# lcd.net
KiCad netlist of a schematic drawn in EAGLE
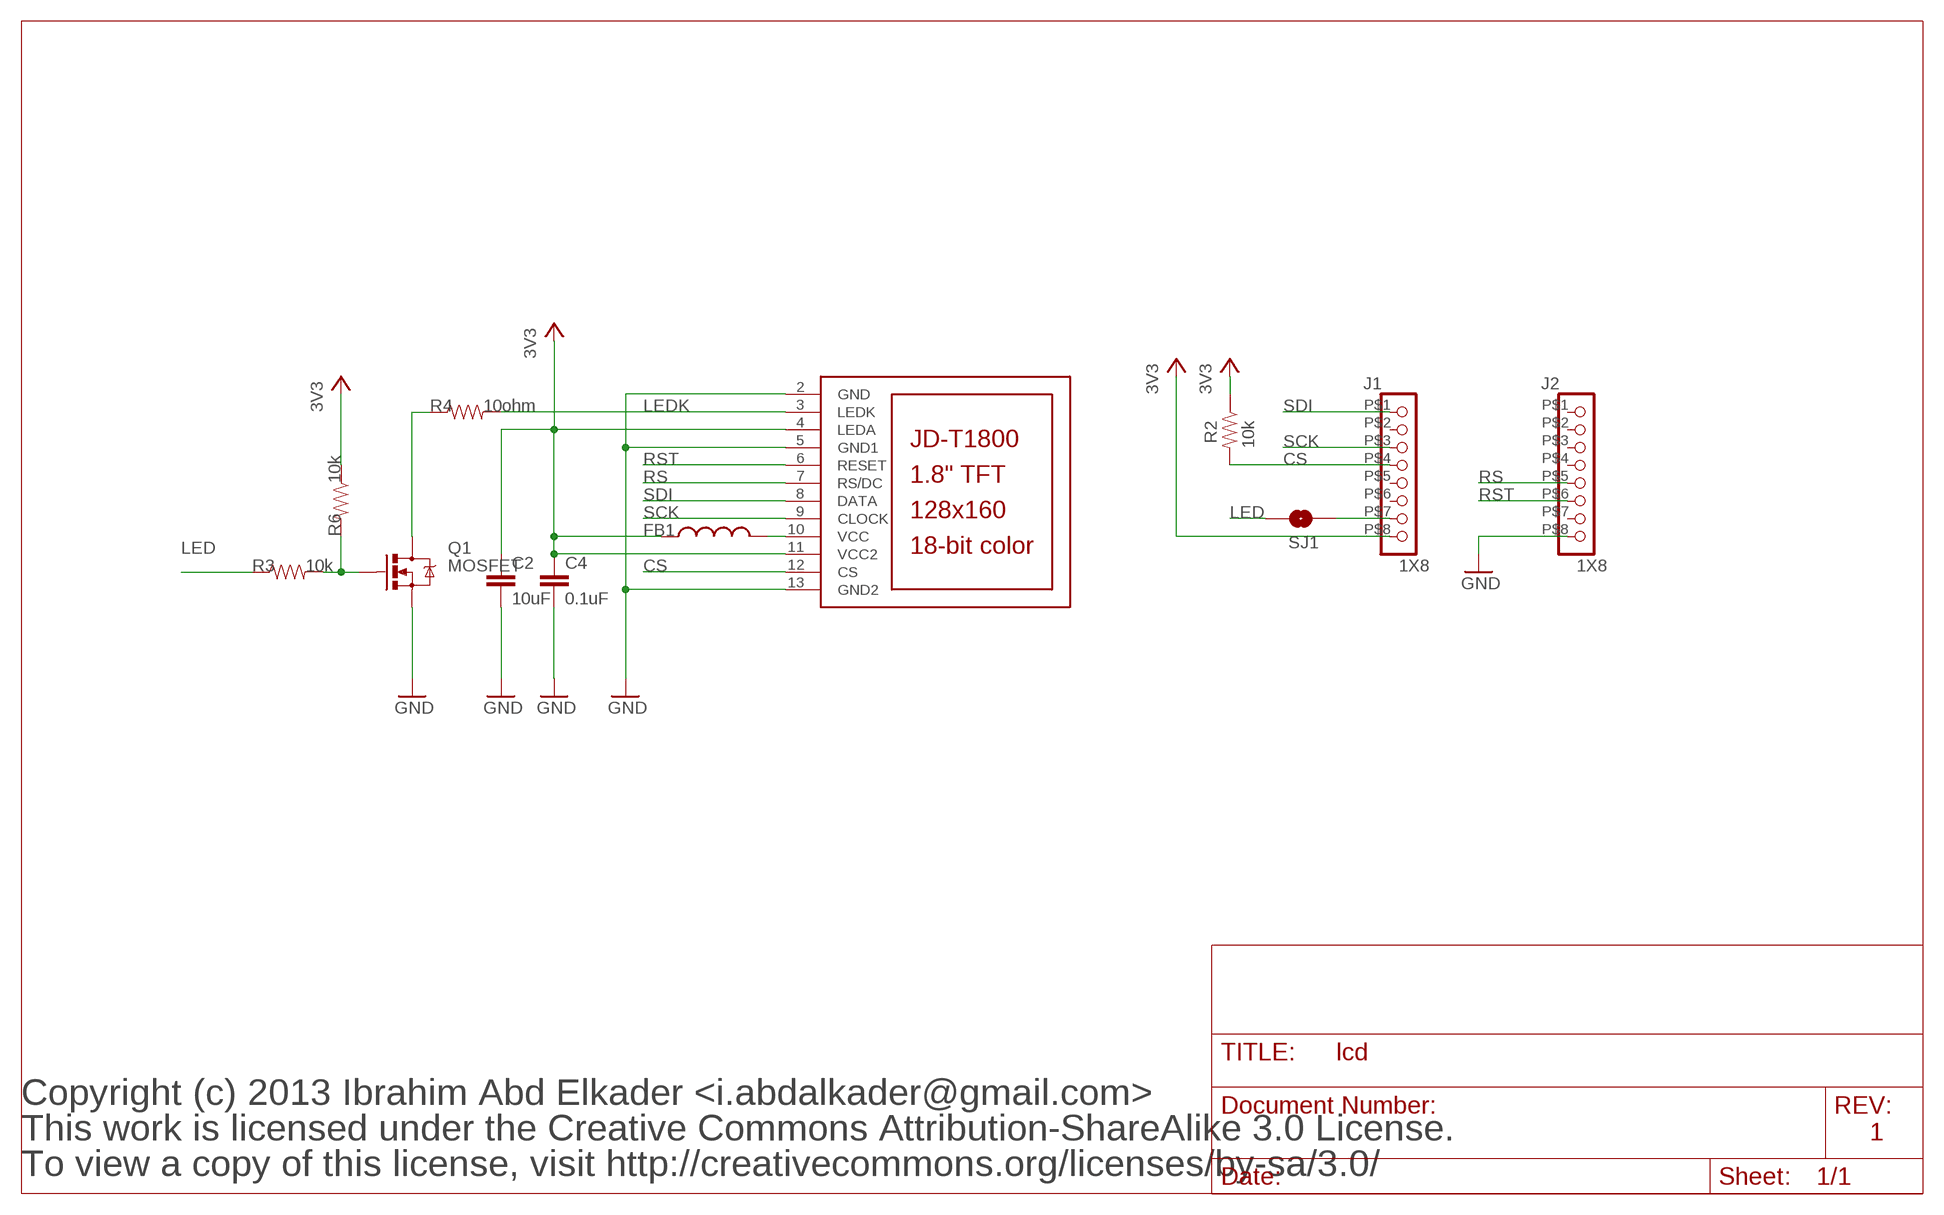
[diagram p0: schematic, sheet 1]

(export (version "E")
  (design (tool "Eeschema 10.0.6"))
  (components
    (comp (ref "C2")
      (value "10uF")
      (footprint "eagle-import:0805")
      (libsource (lib "eagle-import") (part "CAP0805"))
    )
    (comp (ref "C4")
      (value "0.1uF")
      (footprint "eagle-import:0603-CAP")
      (libsource (lib "eagle-import") (part "CAP0603-CAP"))
    )
    (comp (ref "FB1")
      (value "INDUCTOR0603")
      (footprint "eagle-import:0603")
      (libsource (lib "eagle-import") (part "INDUCTOR0603"))
    )
    (comp (ref "J1")
      (value "1X8")
      (footprint "eagle-import:1X8")
      (libsource (lib "eagle-import") (part "1X8"))
    )
    (comp (ref "J2")
      (value "1X8")
      (footprint "eagle-import:1X8")
      (libsource (lib "eagle-import") (part "1X8"))
    )
    (comp (ref "LCD1")
      (value "JD-T1800")
      (footprint "eagle-import:JD-T1800")
      (libsource (lib "eagle-import") (part "JD-T1800"))
    )
    (comp (ref "Q1")
      (value "MOSFET")
      (footprint "eagle-import:SOT23-3")
      (libsource (lib "eagle-import") (part "MOSFET-NCHANNELSMD"))
    )
    (comp (ref "R2")
      (value "10k")
      (footprint "eagle-import:0603-RES")
      (libsource (lib "eagle-import") (part "RESISTOR0603-RES"))
    )
    (comp (ref "R3")
      (value "10k")
      (footprint "eagle-import:0603-RES")
      (libsource (lib "eagle-import") (part "RESISTOR0603-RES"))
    )
    (comp (ref "R4")
      (value "10ohm")
      (footprint "eagle-import:0603-RES")
      (libsource (lib "eagle-import") (part "RESISTOR0603-RES"))
    )
    (comp (ref "R6")
      (value "10k")
      (footprint "eagle-import:0603-RES")
      (libsource (lib "eagle-import") (part "RESISTOR0603-RES"))
    )
    (comp (ref "SJ1")
      (value "SOLDERJUMPERTRACE")
      (footprint "eagle-import:SJ_2S-TRACE")
      (libsource (lib "eagle-import") (part "SOLDERJUMPERTRACE"))
    )
  )
  (nets
    (net (code "1") (name "/CS") (class "Default")
      (node (ref "J1") (pin "P$4") (pinfunction "4_P$4") (pintype "passive"))
      (node (ref "LCD1") (pin "12") (pinfunction "CS_12") (pintype "input"))
      (node (ref "R2") (pin "2") (pinfunction "2_2") (pintype "passive"))
    )
    (net (code "2") (name "/LED") (class "Default")
      (node (ref "R3") (pin "1") (pinfunction "1_1") (pintype "passive"))
      (node (ref "SJ1") (pin "2") (pinfunction "2_2") (pintype "passive"))
    )
    (net (code "3") (name "/LEDK") (class "Default")
      (node (ref "LCD1") (pin "3") (pinfunction "LEDK_3") (pintype "input"))
      (node (ref "R4") (pin "2") (pinfunction "2_2") (pintype "passive"))
    )
    (net (code "4") (name "/RS") (class "Default")
      (node (ref "J2") (pin "P$5") (pinfunction "5_P$5") (pintype "passive"))
      (node (ref "LCD1") (pin "7") (pinfunction "RS/DC_7") (pintype "input"))
    )
    (net (code "5") (name "/RST") (class "Default")
      (node (ref "J2") (pin "P$6") (pinfunction "6_P$6") (pintype "passive"))
      (node (ref "LCD1") (pin "6") (pinfunction "RESET_6") (pintype "input"))
    )
    (net (code "6") (name "/SCK") (class "Default")
      (node (ref "J1") (pin "P$3") (pinfunction "3_P$3") (pintype "passive"))
      (node (ref "LCD1") (pin "9") (pinfunction "CLOCK_9") (pintype "input"))
    )
    (net (code "7") (name "/SDI") (class "Default")
      (node (ref "J1") (pin "P$1") (pinfunction "1_P$1") (pintype "passive"))
      (node (ref "LCD1") (pin "8") (pinfunction "DATA_8") (pintype "bidirectional"))
    )
    (net (code "8") (name "3V3") (class "Default")
      (node (ref "C2") (pin "1") (pinfunction "1_1") (pintype "passive"))
      (node (ref "C4") (pin "1") (pinfunction "1_1") (pintype "passive"))
      (node (ref "FB1") (pin "1") (pinfunction "1_1") (pintype "passive"))
      (node (ref "J1") (pin "P$8") (pinfunction "8_P$8") (pintype "passive"))
      (node (ref "LCD1") (pin "11") (pinfunction "VCC2_11") (pintype "power_in"))
      (node (ref "LCD1") (pin "4") (pinfunction "LEDA_4") (pintype "input"))
      (node (ref "R2") (pin "1") (pinfunction "1_1") (pintype "passive"))
      (node (ref "R6") (pin "1") (pinfunction "1_1") (pintype "passive"))
    )
    (net (code "9") (name "GND") (class "Default")
      (node (ref "C2") (pin "2") (pinfunction "2_2") (pintype "passive"))
      (node (ref "C4") (pin "2") (pinfunction "2_2") (pintype "passive"))
      (node (ref "J2") (pin "P$8") (pinfunction "8_P$8") (pintype "passive"))
      (node (ref "LCD1") (pin "13") (pinfunction "GND2_13") (pintype "power_in"))
      (node (ref "LCD1") (pin "2") (pinfunction "GND_2") (pintype "power_in"))
      (node (ref "LCD1") (pin "5") (pinfunction "GND1_5") (pintype "power_in"))
      (node (ref "Q1") (pin "2") (pinfunction "S_2") (pintype "passive"))
    )
    (net (code "10") (name "Net-(J1-7)") (class "Default")
      (node (ref "J1") (pin "P$7") (pinfunction "7_P$7") (pintype "passive"))
      (node (ref "SJ1") (pin "1") (pinfunction "1_1") (pintype "passive"))
    )
    (net (code "11") (name "Net-(LCD1-VCC)") (class "Default")
      (node (ref "FB1") (pin "2") (pinfunction "2_2") (pintype "passive"))
      (node (ref "LCD1") (pin "10") (pinfunction "VCC_10") (pintype "power_in"))
    )
    (net (code "12") (name "Net-(Q1-D)") (class "Default")
      (node (ref "Q1") (pin "3") (pinfunction "D_3") (pintype "passive"))
      (node (ref "R4") (pin "1") (pinfunction "1_1") (pintype "passive"))
    )
    (net (code "13") (name "Net-(Q1-G)") (class "Default")
      (node (ref "Q1") (pin "1") (pinfunction "G_1") (pintype "passive"))
      (node (ref "R3") (pin "2") (pinfunction "2_2") (pintype "passive"))
      (node (ref "R6") (pin "2") (pinfunction "2_2") (pintype "passive"))
    )
    (net (code "14") (name "unconnected-(J1-2-PadP$2)") (class "Default")
      (node (ref "J1") (pin "P$2") (pinfunction "2_P$2") (pintype "passive"))
    )
    (net (code "15") (name "unconnected-(J1-5-PadP$5)") (class "Default")
      (node (ref "J1") (pin "P$5") (pinfunction "5_P$5") (pintype "passive"))
    )
    (net (code "16") (name "unconnected-(J1-6-PadP$6)") (class "Default")
      (node (ref "J1") (pin "P$6") (pinfunction "6_P$6") (pintype "passive"))
    )
    (net (code "17") (name "unconnected-(J2-1-PadP$1)") (class "Default")
      (node (ref "J2") (pin "P$1") (pinfunction "1_P$1") (pintype "passive"))
    )
    (net (code "18") (name "unconnected-(J2-2-PadP$2)") (class "Default")
      (node (ref "J2") (pin "P$2") (pinfunction "2_P$2") (pintype "passive"))
    )
    (net (code "19") (name "unconnected-(J2-3-PadP$3)") (class "Default")
      (node (ref "J2") (pin "P$3") (pinfunction "3_P$3") (pintype "passive"))
    )
    (net (code "20") (name "unconnected-(J2-4-PadP$4)") (class "Default")
      (node (ref "J2") (pin "P$4") (pinfunction "4_P$4") (pintype "passive"))
    )
    (net (code "21") (name "unconnected-(J2-7-PadP$7)") (class "Default")
      (node (ref "J2") (pin "P$7") (pinfunction "7_P$7") (pintype "passive"))
    )
  )
)
